# MySens-easyESP32b-007.net
KiCad netlist of a schematic drawn in EAGLE
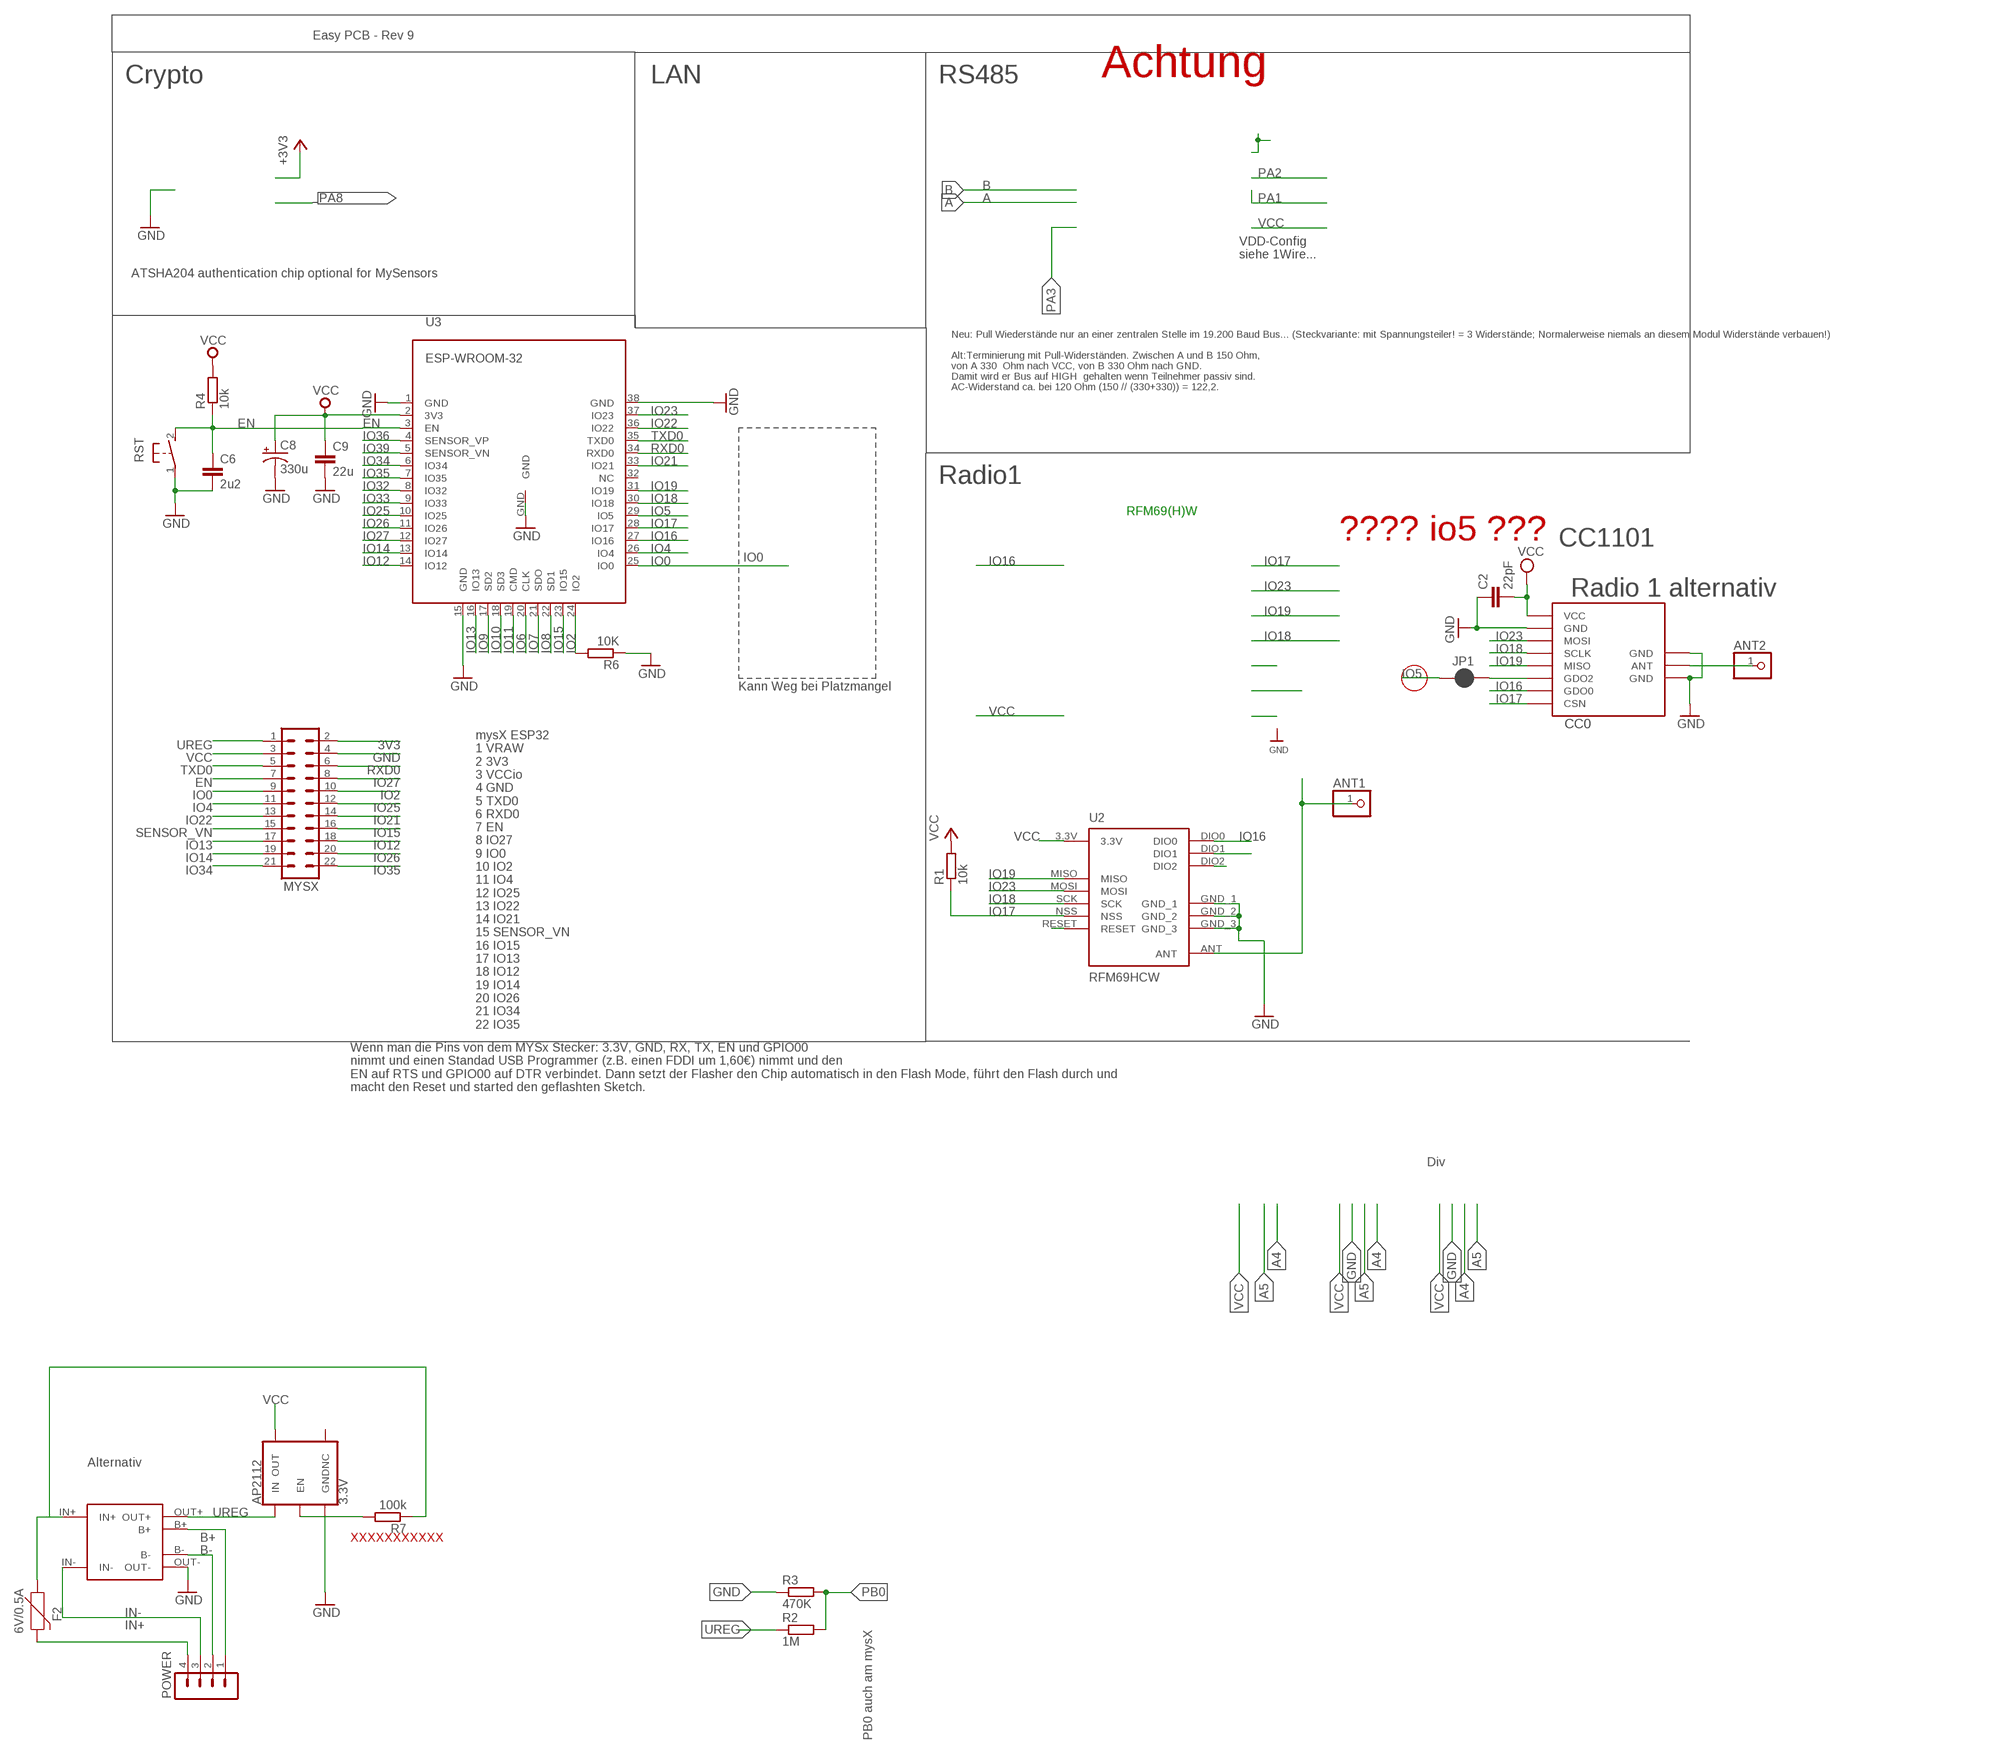
[diagram p0: schematic, sheet 1]

(export (version "E")
  (design (tool "Eeschema 10.0.6"))
  (components
    (comp (ref "ANT1")
      (value "PINHD-1X1")
      (footprint "eagle-import:1X01")
      (libsource (lib "eagle-import") (part "PINHD-1X1"))
    )
    (comp (ref "ANT2")
      (value "PINHD-1X1")
      (footprint "eagle-import:1X01")
      (libsource (lib "eagle-import") (part "PINHD-1X1"))
    )
    (comp (ref "AP2112")
      (value "3.3V")
      (footprint "eagle-import:SOT23-5")
      (libsource (lib "eagle-import") (part "V_REG_AP2112K-3.3V"))
    )
    (comp (ref "C2")
      (value "22pF")
      (footprint "eagle-import:C0805")
      (libsource (lib "eagle-import") (part "C-EUC0805"))
    )
    (comp (ref "C6")
      (value "2u2")
      (footprint "eagle-import:C0805")
      (libsource (lib "eagle-import") (part "rcl@1_C-EUC0805"))
    )
    (comp (ref "C8")
      (value "330u")
      (footprint "eagle-import:VISHAY_C")
      (libsource (lib "eagle-import") (part "CAP_POLSMD"))
    )
    (comp (ref "C9")
      (value "22u")
      (footprint "eagle-import:C0805")
      (libsource (lib "eagle-import") (part "rcl@1_C-EUC0805"))
    )
    (comp (ref "CC0")
      (value "CC1101")
      (footprint "eagle-import:CC1101_MODULE1_SMD")
      (libsource (lib "eagle-import") (part "CC1101_MODULE1SMD"))
    )
    (comp (ref "F2")
      (value "6V/0.5A")
      (footprint "eagle-import:1206")
      (libsource (lib "eagle-import") (part "PPTC_HALF-AMP"))
    )
    (comp (ref "JP1")
      (value "JUMPER-SMT_2_NC_PASTE_NO-SILK")
      (footprint "eagle-import:SMT-JUMPER_2_NC_PASTE_NO-SILK")
      (libsource (lib "eagle-import") (part "JUMPER-SMT_2_NC_PASTE_NO-SILK"))
    )
    (comp (ref "MYSX")
      (value "MA11-2")
      (footprint "eagle-import:MA11-2")
      (libsource (lib "eagle-import") (part "MA11-2"))
    )
    (comp (ref "POWER")
      (value "MA04-1")
      (footprint "eagle-import:MA04-1")
      (libsource (lib "eagle-import") (part "MA04-1"))
    )
    (comp (ref "R1")
      (value "10k")
      (footprint "eagle-import:M0805")
      (libsource (lib "eagle-import") (part "R-EU_M0805"))
    )
    (comp (ref "R2")
      (value "1M")
      (footprint "eagle-import:M0805")
      (libsource (lib "eagle-import") (part "R-EU_M0805"))
    )
    (comp (ref "R3")
      (value "470K")
      (footprint "eagle-import:M0805")
      (libsource (lib "eagle-import") (part "R-EU_M0805"))
    )
    (comp (ref "R4")
      (value "10k")
      (footprint "eagle-import:M0805")
      (libsource (lib "eagle-import") (part "rcl@1_R-EU_M0805"))
    )
    (comp (ref "R6")
      (value "10K")
      (footprint "eagle-import:M0805")
      (libsource (lib "eagle-import") (part "R-EU_M0805"))
    )
    (comp (ref "R7")
      (value "100k")
      (footprint "eagle-import:M0805")
      (libsource (lib "eagle-import") (part "R-EU_M0805"))
    )
    (comp (ref "RST")
      (value "DTSM-3")
      (footprint "eagle-import:DTSM-3")
      (libsource (lib "eagle-import") (part "DTSM-3"))
    )
    (comp (ref "TP4056")
      (value "TP4056-MODULE")
      (footprint "eagle-import:TP4056-LITHIUM-PROTECTED-MODULE")
      (libsource (lib "eagle-import") (part "TP4056-MODULE"))
    )
    (comp (ref "U2")
      (value "RFM69HCW")
      (footprint "eagle-import:RFM69HCW-XXXS2")
      (libsource (lib "eagle-import") (part "RFM69HCW"))
    )
    (comp (ref "U3")
      (value "ESP-WROOM-32")
      (footprint "eagle-import:ESP-WROOM-32")
      (libsource (lib "eagle-import") (part "ESP-WROOM-32"))
    )
  )
  (nets
    (net (code "2") (name "/3V3") (class "Default")
      (node (ref "MYSX") (pin "2") (pinfunction "2_2") (pintype "passive"))
    )
    (net (code "3") (name "/B+") (class "Default")
      (node (ref "POWER") (pin "1") (pinfunction "1_1") (pintype "passive"))
      (node (ref "TP4056") (pin "B+") (pinfunction "B+_B+") (pintype "power_in"))
    )
    (net (code "4") (name "/B-") (class "Default")
      (node (ref "POWER") (pin "2") (pinfunction "2_2") (pintype "passive"))
      (node (ref "TP4056") (pin "B-") (pinfunction "B-_B-") (pintype "power_in"))
    )
    (net (code "5") (name "/EN") (class "Default")
      (node (ref "C6") (pin "1") (pinfunction "1_1") (pintype "passive"))
      (node (ref "MYSX") (pin "7") (pinfunction "7_7") (pintype "passive"))
      (node (ref "R4") (pin "1") (pinfunction "1_1") (pintype "passive"))
      (node (ref "RST") (pin "2") (pinfunction "2_2") (pintype "passive"))
      (node (ref "U3") (pin "3") (pinfunction "EN_3") (pintype "bidirectional"))
    )
    (net (code "6") (name "/IN+") (class "Default")
      (node (ref "F2") (pin "2") (pinfunction "2_2") (pintype "bidirectional"))
      (node (ref "POWER") (pin "4") (pinfunction "4_4") (pintype "passive"))
    )
    (net (code "7") (name "/IN-") (class "Default")
      (node (ref "POWER") (pin "3") (pinfunction "3_3") (pintype "passive"))
      (node (ref "TP4056") (pin "IN-") (pinfunction "IN-_IN-") (pintype "power_in"))
    )
    (net (code "8") (name "/IO0") (class "Default")
      (node (ref "MYSX") (pin "9") (pinfunction "9_9") (pintype "passive"))
      (node (ref "U3") (pin "25") (pinfunction "IO0_25") (pintype "bidirectional"))
    )
    (net (code "9") (name "/IO2") (class "Default")
      (node (ref "MYSX") (pin "10") (pinfunction "10_10") (pintype "passive"))
      (node (ref "R6") (pin "2") (pinfunction "2_2") (pintype "passive"))
      (node (ref "U3") (pin "24") (pinfunction "IO2_24") (pintype "bidirectional"))
    )
    (net (code "10") (name "/IO4") (class "Default")
      (node (ref "MYSX") (pin "11") (pinfunction "11_11") (pintype "passive"))
      (node (ref "U3") (pin "26") (pinfunction "IO4_26") (pintype "bidirectional"))
    )
    (net (code "11") (name "/IO5") (class "Default")
      (node (ref "JP1") (pin "1") (pinfunction "1_1") (pintype "passive"))
      (node (ref "U3") (pin "29") (pinfunction "IO5_29") (pintype "bidirectional"))
    )
    (net (code "12") (name "/IO6") (class "Default")
      (node (ref "U3") (pin "20") (pinfunction "CLK_20") (pintype "bidirectional"))
    )
    (net (code "13") (name "/IO7") (class "Default")
      (node (ref "U3") (pin "21") (pinfunction "SDO_21") (pintype "bidirectional"))
    )
    (net (code "14") (name "/IO8") (class "Default")
      (node (ref "U3") (pin "22") (pinfunction "SD1_22") (pintype "bidirectional"))
    )
    (net (code "15") (name "/IO9") (class "Default")
      (node (ref "U3") (pin "17") (pinfunction "SD2_17") (pintype "bidirectional"))
    )
    (net (code "16") (name "/IO10") (class "Default")
      (node (ref "U3") (pin "18") (pinfunction "SD3_18") (pintype "bidirectional"))
    )
    (net (code "17") (name "/IO11") (class "Default")
      (node (ref "U3") (pin "19") (pinfunction "CMD_19") (pintype "bidirectional"))
    )
    (net (code "18") (name "/IO12") (class "Default")
      (node (ref "MYSX") (pin "18") (pinfunction "18_18") (pintype "passive"))
      (node (ref "U3") (pin "14") (pinfunction "IO12_14") (pintype "bidirectional"))
    )
    (net (code "19") (name "/IO13") (class "Default")
      (node (ref "MYSX") (pin "17") (pinfunction "17_17") (pintype "passive"))
      (node (ref "U3") (pin "16") (pinfunction "IO13_16") (pintype "bidirectional"))
    )
    (net (code "20") (name "/IO14") (class "Default")
      (node (ref "MYSX") (pin "19") (pinfunction "19_19") (pintype "passive"))
      (node (ref "U3") (pin "13") (pinfunction "IO14_13") (pintype "bidirectional"))
    )
    (net (code "21") (name "/IO15") (class "Default")
      (node (ref "MYSX") (pin "16") (pinfunction "16_16") (pintype "passive"))
      (node (ref "U3") (pin "23") (pinfunction "IO15_23") (pintype "bidirectional"))
    )
    (net (code "22") (name "/IO16") (class "Default")
      (node (ref "CC0") (pin "GDO0") (pinfunction "GDO0_GDO0") (pintype "bidirectional"))
      (node (ref "U2") (pin "DIO0") (pinfunction "DIO0_DIO0") (pintype "bidirectional"))
      (node (ref "U3") (pin "27") (pinfunction "IO16_27") (pintype "bidirectional"))
    )
    (net (code "23") (name "/IO17") (class "Default")
      (node (ref "CC0") (pin "CSN") (pinfunction "CSN_CSN") (pintype "bidirectional"))
      (node (ref "R1") (pin "1") (pinfunction "1_1") (pintype "passive"))
      (node (ref "U2") (pin "NSS") (pinfunction "NSS_NSS") (pintype "input"))
      (node (ref "U3") (pin "28") (pinfunction "IO17_28") (pintype "bidirectional"))
    )
    (net (code "24") (name "/IO18") (class "Default")
      (node (ref "CC0") (pin "SCLK") (pinfunction "SCLK_SCLK") (pintype "bidirectional"))
      (node (ref "U2") (pin "SCK") (pinfunction "SCK_SCK") (pintype "input"))
      (node (ref "U3") (pin "30") (pinfunction "IO18_30") (pintype "bidirectional"))
    )
    (net (code "25") (name "/IO19") (class "Default")
      (node (ref "CC0") (pin "MISO") (pinfunction "MISO_MISO") (pintype "bidirectional"))
      (node (ref "U2") (pin "MISO") (pinfunction "MISO_MISO") (pintype "bidirectional"))
      (node (ref "U3") (pin "31") (pinfunction "IO19_31") (pintype "bidirectional"))
    )
    (net (code "26") (name "/IO21") (class "Default")
      (node (ref "MYSX") (pin "14") (pinfunction "14_14") (pintype "passive"))
      (node (ref "U3") (pin "33") (pinfunction "IO21_33") (pintype "bidirectional"))
    )
    (net (code "27") (name "/IO22") (class "Default")
      (node (ref "MYSX") (pin "13") (pinfunction "13_13") (pintype "passive"))
      (node (ref "U3") (pin "36") (pinfunction "IO22_36") (pintype "bidirectional"))
    )
    (net (code "28") (name "/IO23") (class "Default")
      (node (ref "CC0") (pin "MOSI") (pinfunction "MOSI_MOSI") (pintype "bidirectional"))
      (node (ref "U2") (pin "MOSI") (pinfunction "MOSI_MOSI") (pintype "input"))
      (node (ref "U3") (pin "37") (pinfunction "IO23_37") (pintype "bidirectional"))
    )
    (net (code "29") (name "/IO25") (class "Default")
      (node (ref "MYSX") (pin "12") (pinfunction "12_12") (pintype "passive"))
      (node (ref "U3") (pin "10") (pinfunction "IO25_10") (pintype "bidirectional"))
    )
    (net (code "30") (name "/IO26") (class "Default")
      (node (ref "MYSX") (pin "20") (pinfunction "20_20") (pintype "passive"))
      (node (ref "U3") (pin "11") (pinfunction "IO26_11") (pintype "bidirectional"))
    )
    (net (code "31") (name "/IO27") (class "Default")
      (node (ref "MYSX") (pin "8") (pinfunction "8_8") (pintype "passive"))
      (node (ref "U3") (pin "12") (pinfunction "IO27_12") (pintype "bidirectional"))
    )
    (net (code "32") (name "/IO32") (class "Default")
      (node (ref "U3") (pin "8") (pinfunction "IO32_8") (pintype "bidirectional"))
    )
    (net (code "33") (name "/IO33") (class "Default")
      (node (ref "U3") (pin "9") (pinfunction "IO33_9") (pintype "bidirectional"))
    )
    (net (code "34") (name "/IO34") (class "Default")
      (node (ref "MYSX") (pin "21") (pinfunction "21_21") (pintype "passive"))
      (node (ref "U3") (pin "6") (pinfunction "IO34_6") (pintype "bidirectional"))
    )
    (net (code "35") (name "/IO35") (class "Default")
      (node (ref "MYSX") (pin "22") (pinfunction "22_22") (pintype "passive"))
      (node (ref "U3") (pin "7") (pinfunction "IO35_7") (pintype "bidirectional"))
    )
    (net (code "36") (name "/IO36") (class "Default")
      (node (ref "U3") (pin "4") (pinfunction "SENSOR_VP_4") (pintype "bidirectional"))
    )
    (net (code "37") (name "/IO39") (class "Default")
      (node (ref "U3") (pin "5") (pinfunction "SENSOR_VN_5") (pintype "bidirectional"))
    )
    (net (code "41") (name "/RXD0") (class "Default")
      (node (ref "MYSX") (pin "6") (pinfunction "6_6") (pintype "passive"))
      (node (ref "U3") (pin "34") (pinfunction "RXD0_34") (pintype "bidirectional"))
    )
    (net (code "42") (name "/SENSOR_VN") (class "Default")
      (node (ref "MYSX") (pin "15") (pinfunction "15_15") (pintype "passive"))
    )
    (net (code "43") (name "/TXD0") (class "Default")
      (node (ref "MYSX") (pin "5") (pinfunction "5_5") (pintype "passive"))
      (node (ref "U3") (pin "35") (pinfunction "TXD0_35") (pintype "bidirectional"))
    )
    (net (code "48") (name "GND") (class "Default")
      (node (ref "AP2112") (pin "2") (pinfunction "GND_2") (pintype "input"))
      (node (ref "C2") (pin "1") (pinfunction "1_1") (pintype "passive"))
      (node (ref "C6") (pin "2") (pinfunction "2_2") (pintype "passive"))
      (node (ref "C8") (pin "-") (pinfunction "-_-") (pintype "passive"))
      (node (ref "C9") (pin "2") (pinfunction "2_2") (pintype "passive"))
      (node (ref "CC0") (pin "GND@0") (pinfunction "GND_GND@0") (pintype "power_in"))
      (node (ref "CC0") (pin "GND@1") (pinfunction "GND_GND@1") (pintype "power_in"))
      (node (ref "CC0") (pin "GND@2") (pinfunction "GND_GND@2") (pintype "power_in"))
      (node (ref "MYSX") (pin "4") (pinfunction "4_4") (pintype "passive"))
      (node (ref "R3") (pin "1") (pinfunction "1_1") (pintype "passive"))
      (node (ref "R6") (pin "1") (pinfunction "1_1") (pintype "passive"))
      (node (ref "RST") (pin "1") (pinfunction "1_1") (pintype "passive"))
      (node (ref "TP4056") (pin "OUT-") (pinfunction "OUT-_OUT-") (pintype "power_in"))
      (node (ref "U2") (pin "GND_1") (pinfunction "GND_1_GND_1") (pintype "power_in"))
      (node (ref "U2") (pin "GND_2") (pinfunction "GND_2_GND_2") (pintype "power_in"))
      (node (ref "U2") (pin "GND_3") (pinfunction "GND_3_GND_3") (pintype "power_in"))
      (node (ref "U3") (pin "1") (pinfunction "GND_1") (pintype "bidirectional"))
      (node (ref "U3") (pin "15") (pinfunction "GND_15") (pintype "bidirectional"))
      (node (ref "U3") (pin "38") (pinfunction "GND_38") (pintype "bidirectional"))
      (node (ref "U3") (pin "GND") (pinfunction "GND_GND") (pintype "bidirectional"))
    )
    (net (code "49") (name "Net-(ANT1-Pad1)") (class "Default")
      (node (ref "ANT1") (pin "1") (pinfunction "1_1") (pintype "passive"))
      (node (ref "U2") (pin "ANT") (pinfunction "ANT_ANT") (pintype "passive"))
    )
    (net (code "50") (name "Net-(ANT2-Pad1)") (class "Default")
      (node (ref "ANT2") (pin "1") (pinfunction "1_1") (pintype "passive"))
      (node (ref "CC0") (pin "ANT") (pinfunction "ANT_ANT") (pintype "output"))
    )
    (net (code "51") (name "Net-(AP2112-EN)") (class "Default")
      (node (ref "AP2112") (pin "3") (pinfunction "EN_3") (pintype "input"))
      (node (ref "R7") (pin "2") (pinfunction "2_2") (pintype "passive"))
    )
    (net (code "52") (name "Net-(CC0-PadGDO2)") (class "Default")
      (node (ref "CC0") (pin "GDO2") (pinfunction "GDO2_GDO2") (pintype "bidirectional"))
      (node (ref "JP1") (pin "2") (pinfunction "2_2") (pintype "passive"))
    )
    (net (code "53") (name "Net-(F2-Pad1)") (class "Default")
      (node (ref "F2") (pin "1") (pinfunction "1_1") (pintype "bidirectional"))
      (node (ref "R7") (pin "1") (pinfunction "1_1") (pintype "passive"))
      (node (ref "TP4056") (pin "IN+") (pinfunction "IN+_IN+") (pintype "power_in"))
    )
    (net (code "55") (name "PB0") (class "Default")
      (node (ref "R2") (pin "2") (pinfunction "2_2") (pintype "passive"))
      (node (ref "R3") (pin "2") (pinfunction "2_2") (pintype "passive"))
    )
    (net (code "56") (name "UREG") (class "Default")
      (node (ref "AP2112") (pin "1") (pinfunction "IN_1") (pintype "input"))
      (node (ref "MYSX") (pin "1") (pinfunction "1_1") (pintype "passive"))
      (node (ref "R2") (pin "1") (pinfunction "1_1") (pintype "passive"))
      (node (ref "TP4056") (pin "OUT+") (pinfunction "OUT+_OUT+") (pintype "power_in"))
    )
    (net (code "57") (name "VCC") (class "Default")
      (node (ref "AP2112") (pin "5") (pinfunction "OUT_5") (pintype "passive"))
      (node (ref "C2") (pin "2") (pinfunction "2_2") (pintype "passive"))
      (node (ref "C8") (pin "+") (pinfunction "+_+") (pintype "passive"))
      (node (ref "C9") (pin "1") (pinfunction "1_1") (pintype "passive"))
      (node (ref "CC0") (pin "VCC") (pinfunction "VCC_VCC") (pintype "power_in"))
      (node (ref "MYSX") (pin "3") (pinfunction "3_3") (pintype "passive"))
      (node (ref "R1") (pin "2") (pinfunction "2_2") (pintype "passive"))
      (node (ref "R4") (pin "2") (pinfunction "2_2") (pintype "passive"))
      (node (ref "U2") (pin "3.3V") (pinfunction "3.3V_3.3V") (pintype "power_in"))
      (node (ref "U3") (pin "2") (pinfunction "3V3_2") (pintype "bidirectional"))
    )
    (net (code "58") (name "unconnected-(AP2112-NC-Pad4)") (class "Default")
      (node (ref "AP2112") (pin "4") (pinfunction "NC_4") (pintype "no_connect"))
    )
    (net (code "59") (name "unconnected-(U2-PadDIO1)") (class "Default")
      (node (ref "U2") (pin "DIO1") (pinfunction "DIO1_DIO1") (pintype "bidirectional"))
    )
    (net (code "60") (name "unconnected-(U2-PadDIO2)") (class "Default")
      (node (ref "U2") (pin "DIO2") (pinfunction "DIO2_DIO2") (pintype "bidirectional"))
    )
    (net (code "61") (name "unconnected-(U2-PadRESET)") (class "Default")
      (node (ref "U2") (pin "RESET") (pinfunction "RESET_RESET") (pintype "input"))
    )
    (net (code "62") (name "unconnected-(U3-NC-Pad32)") (class "Default")
      (node (ref "U3") (pin "32") (pinfunction "NC_32") (pintype "bidirectional"))
    )
  )
)
